# SheetPIC80_A9377.net
KiCad netlist of a schematic drawn in Altium Designer
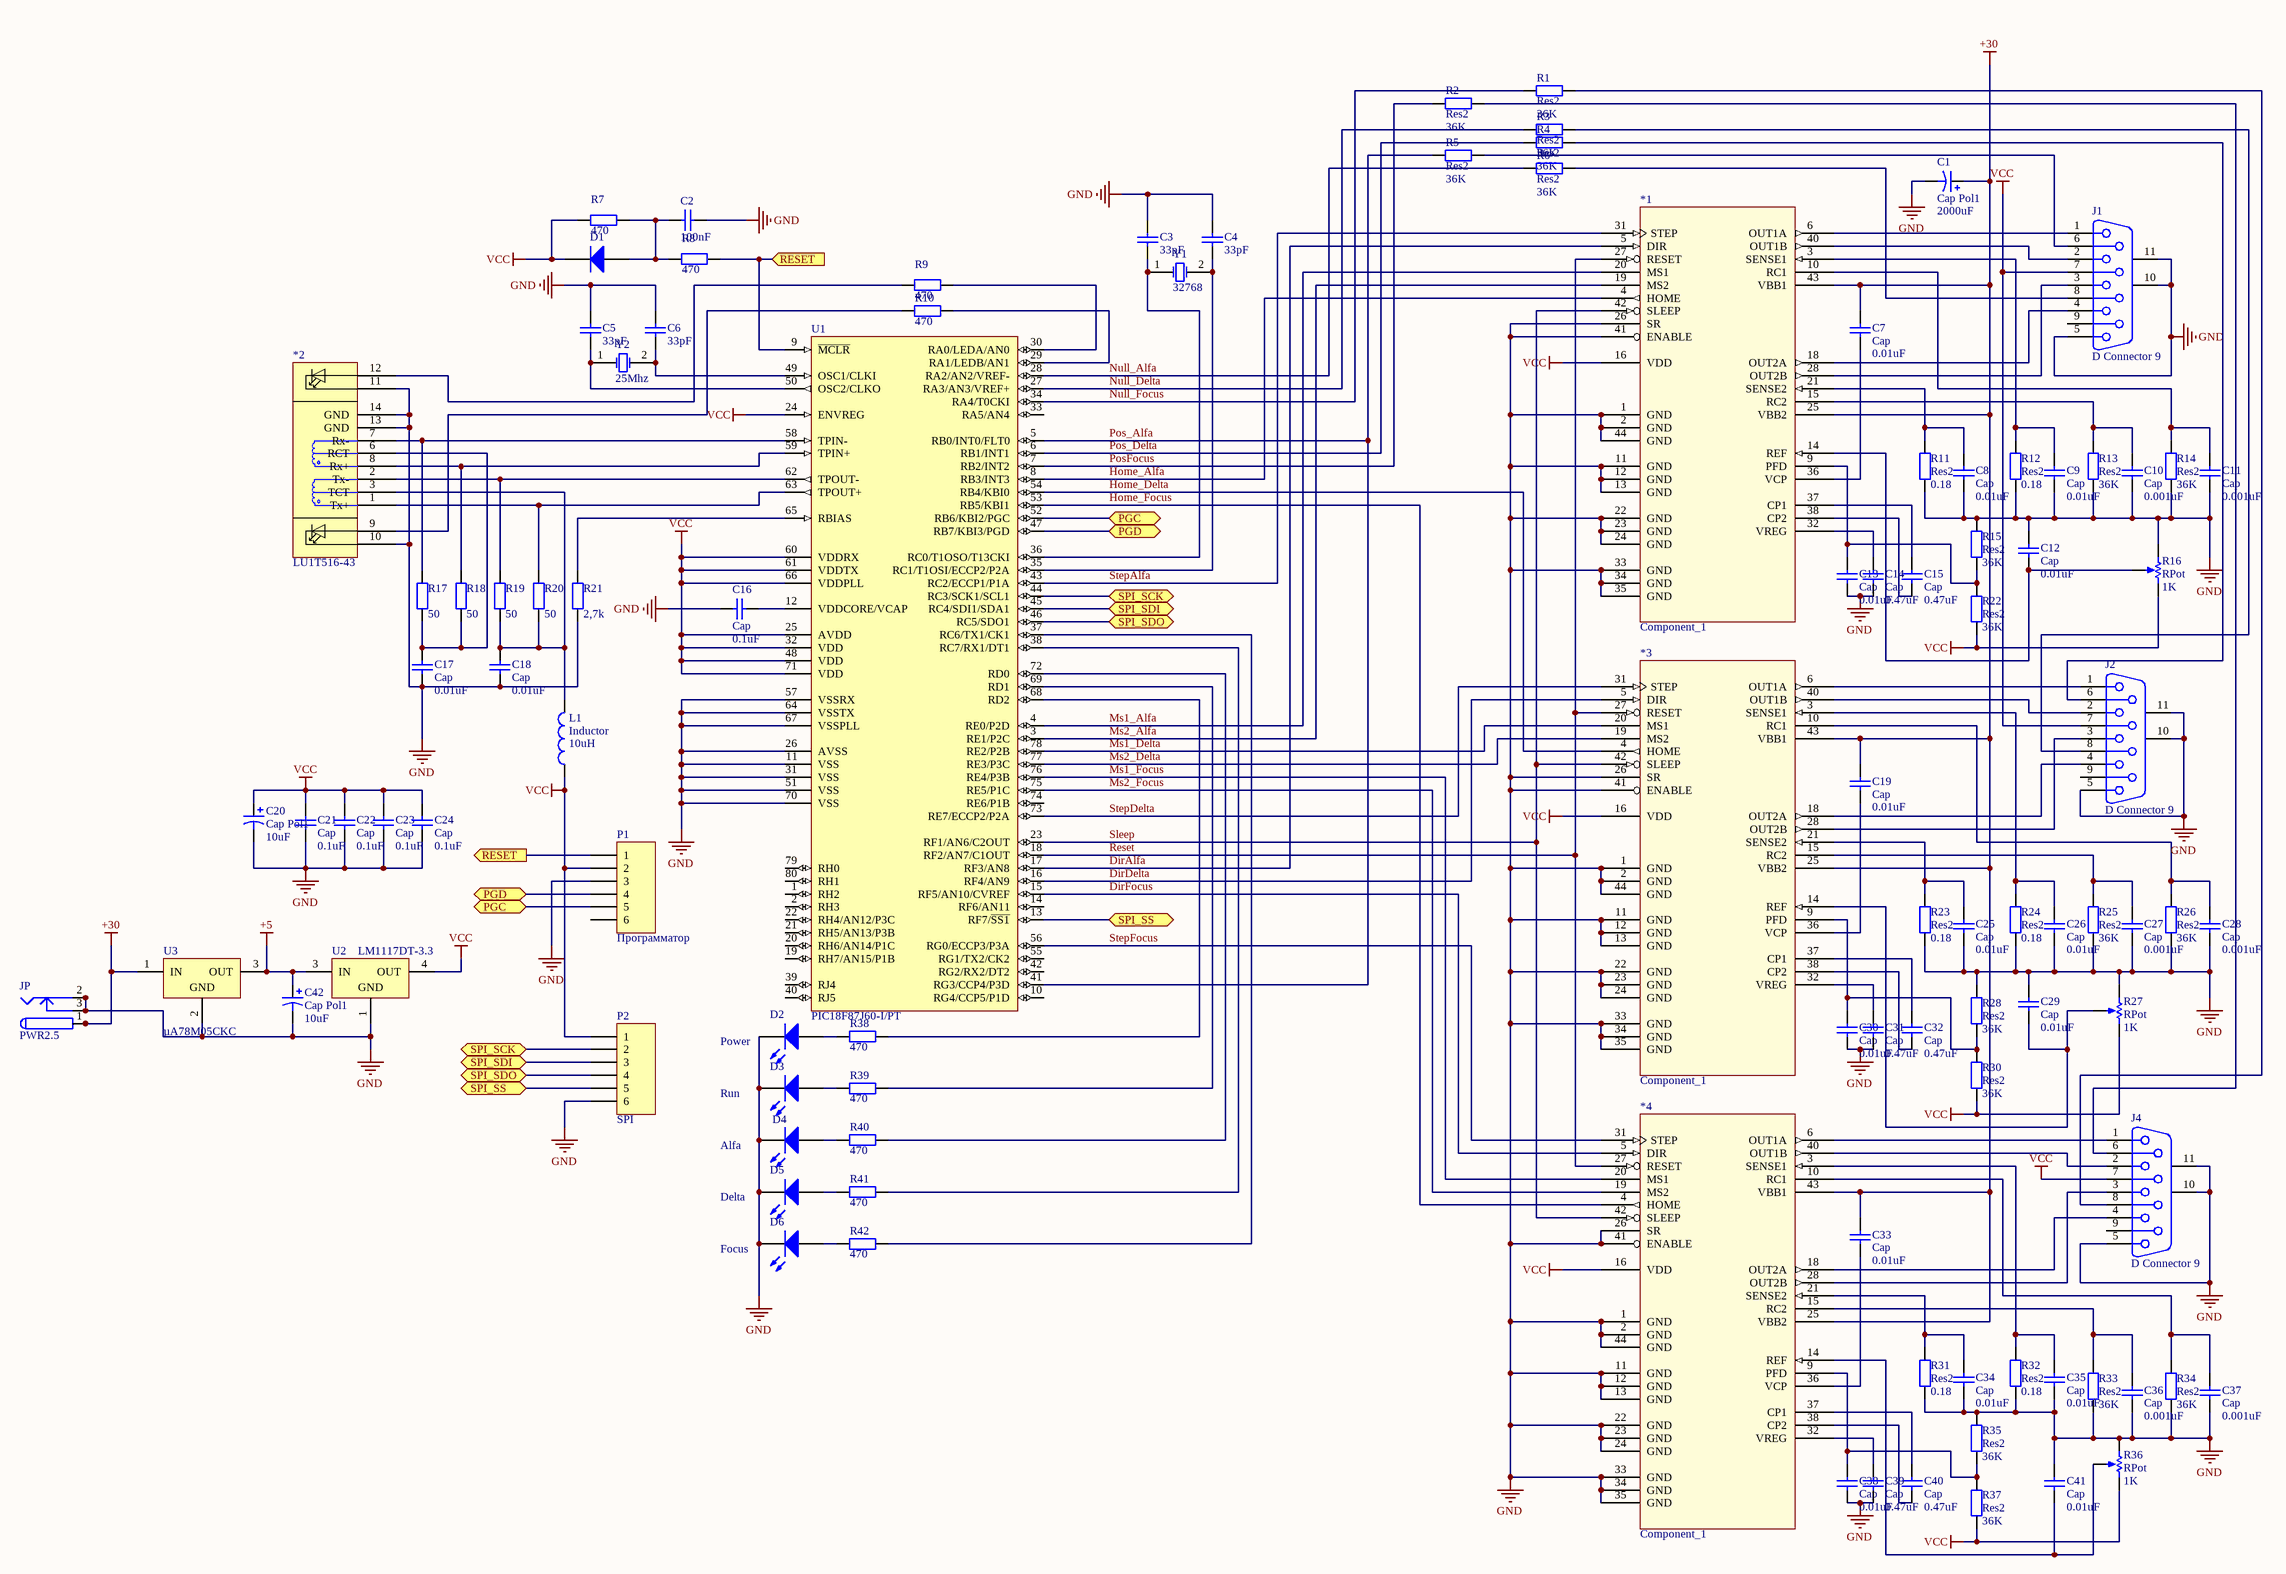
[diagram p0: SheetPIC80_A9377.SchDoc]

(export (version "E")
  (design (tool "Eeschema 10.0.6"))
  (components
    (comp (ref "*1")
      (value "Component_1")
      (footprint "PLCC-44AM")
      (libsource (lib "Allegro Stepper Control") (part "Component_1"))
    )
    (comp (ref "*2")
      (value "LU1T516-43")
      (footprint "EthernetCON")
      (libsource (lib "Ethernet") (part "LU1T516-43"))
    )
    (comp (ref "*3")
      (value "Component_1")
      (footprint "PLCC-44AM")
      (libsource (lib "Allegro Stepper Control") (part "Component_1"))
    )
    (comp (ref "*4")
      (value "Component_1")
      (footprint "PLCC-44AM")
      (libsource (lib "Allegro Stepper Control") (part "Component_1"))
    )
    (comp (ref "C1")
      (value "Cap Pol1")
      (footprint "RB7.6-15")
      (description "Polarized Capacitor (Radial)")
      (fields (field (name "ALTIUM_VALUE") "2000uF") (field (name "PUBLISHER") "Altium Limited"))
      (libsource (lib "Miscellaneous Devices") (part "Cap Pol1"))
    )
    (comp (ref "C2")
      (value "100nF")
      (footprint "CAPC3225N")
      (description "Capacitor")
      (fields (field (name "Comment") "Cap") (field (name "PUBLISHER") "Altium Limited"))
      (libsource (lib "Miscellaneous Devices") (part "Cap"))
    )
    (comp (ref "C3")
      (value "33pF")
      (footprint "CAPC2012L")
      (description "Capacitor")
      (fields (field (name "Comment") "Cap") (field (name "PUBLISHER") "Altium Limited"))
      (libsource (lib "Miscellaneous Devices") (part "Cap"))
    )
    (comp (ref "C4")
      (value "33pF")
      (footprint "CAPC2012L")
      (description "Capacitor")
      (fields (field (name "Comment") "Cap") (field (name "PUBLISHER") "Altium Limited"))
      (libsource (lib "Miscellaneous Devices") (part "Cap"))
    )
    (comp (ref "C5")
      (value "33pF")
      (footprint "CAPC2012L")
      (description "Capacitor")
      (fields (field (name "Comment") "Cap") (field (name "PUBLISHER") "Altium Limited"))
      (libsource (lib "Miscellaneous Devices") (part "Cap"))
    )
    (comp (ref "C6")
      (value "33pF")
      (footprint "CAPC2012L")
      (description "Capacitor")
      (fields (field (name "Comment") "Cap") (field (name "PUBLISHER") "Altium Limited"))
      (libsource (lib "Miscellaneous Devices") (part "Cap"))
    )
    (comp (ref "C7")
      (value "Cap")
      (footprint "RESC3225L")
      (description "Capacitor")
      (fields (field (name "ALTIUM_VALUE") "0.01uF") (field (name "PUBLISHER") "Altium Limited"))
      (libsource (lib "Miscellaneous Devices") (part "Cap"))
    )
    (comp (ref "C8")
      (value "Cap")
      (footprint "RESC3225L")
      (description "Capacitor")
      (fields (field (name "ALTIUM_VALUE") "0.01uF") (field (name "PUBLISHER") "Altium Limited"))
      (libsource (lib "Miscellaneous Devices") (part "Cap"))
    )
    (comp (ref "C9")
      (value "Cap")
      (footprint "RESC3225L")
      (description "Capacitor")
      (fields (field (name "ALTIUM_VALUE") "0.01uF") (field (name "PUBLISHER") "Altium Limited"))
      (libsource (lib "Miscellaneous Devices") (part "Cap"))
    )
    (comp (ref "C10")
      (value "Cap")
      (footprint "CAPC2012L")
      (description "Capacitor")
      (fields (field (name "ALTIUM_VALUE") "0.001uF") (field (name "PUBLISHER") "Altium Limited"))
      (libsource (lib "Miscellaneous Devices") (part "Cap"))
    )
    (comp (ref "C11")
      (value "Cap")
      (footprint "CAPC2012L")
      (description "Capacitor")
      (fields (field (name "ALTIUM_VALUE") "0.001uF") (field (name "PUBLISHER") "Altium Limited"))
      (libsource (lib "Miscellaneous Devices") (part "Cap"))
    )
    (comp (ref "C12")
      (value "Cap")
      (footprint "CAPC2012L")
      (description "Capacitor")
      (fields (field (name "ALTIUM_VALUE") "0.01uF") (field (name "PUBLISHER") "Altium Limited"))
      (libsource (lib "Miscellaneous Devices") (part "Cap"))
    )
    (comp (ref "C13")
      (value "Cap")
      (footprint "RESC2012N")
      (description "Capacitor")
      (fields (field (name "ALTIUM_VALUE") "0.01uF") (field (name "PUBLISHER") "Altium Limited"))
      (libsource (lib "Miscellaneous Devices") (part "Cap"))
    )
    (comp (ref "C14")
      (value "Cap")
      (footprint "RESC3225L")
      (description "Capacitor")
      (fields (field (name "ALTIUM_VALUE") "0.47uF") (field (name "PUBLISHER") "Altium Limited"))
      (libsource (lib "Miscellaneous Devices") (part "Cap"))
    )
    (comp (ref "C15")
      (value "Cap")
      (footprint "RESC3225L")
      (description "Capacitor")
      (fields (field (name "ALTIUM_VALUE") "0.47uF") (field (name "PUBLISHER") "Altium Limited"))
      (libsource (lib "Miscellaneous Devices") (part "Cap"))
    )
    (comp (ref "C16")
      (value "Cap")
      (footprint "CAPC3225L")
      (description "Capacitor")
      (fields (field (name "ALTIUM_VALUE") "0.1uF") (field (name "PUBLISHER") "Altium Limited"))
      (libsource (lib "Miscellaneous Devices") (part "Cap"))
    )
    (comp (ref "C17")
      (value "Cap")
      (footprint "CAPC3216L")
      (description "Capacitor")
      (fields (field (name "ALTIUM_VALUE") "0.01uF") (field (name "PUBLISHER") "Altium Limited"))
      (libsource (lib "Miscellaneous Devices") (part "Cap"))
    )
    (comp (ref "C18")
      (value "Cap")
      (footprint "CAPC3216L")
      (description "Capacitor")
      (fields (field (name "ALTIUM_VALUE") "0.01uF") (field (name "PUBLISHER") "Altium Limited"))
      (libsource (lib "Miscellaneous Devices") (part "Cap"))
    )
    (comp (ref "C19")
      (value "Cap")
      (footprint "RESC3225L")
      (description "Capacitor")
      (fields (field (name "ALTIUM_VALUE") "0.01uF") (field (name "PUBLISHER") "Altium Limited"))
      (libsource (lib "Miscellaneous Devices") (part "Cap"))
    )
    (comp (ref "C20")
      (value "Cap Pol1")
      (footprint "CAPPR5-5x5")
      (description "Polarized Capacitor (Radial)")
      (fields (field (name "ALTIUM_VALUE") "10uF") (field (name "PUBLISHER") "Altium Limited"))
      (libsource (lib "Miscellaneous Devices") (part "Cap Pol1"))
    )
    (comp (ref "C21")
      (value "Cap")
      (footprint "CAPC3225L")
      (description "Capacitor")
      (fields (field (name "ALTIUM_VALUE") "0.1uF") (field (name "PUBLISHER") "Altium Limited"))
      (libsource (lib "Miscellaneous Devices") (part "Cap"))
    )
    (comp (ref "C22")
      (value "Cap")
      (footprint "CAPC3225L")
      (description "Capacitor")
      (fields (field (name "ALTIUM_VALUE") "0.1uF") (field (name "PUBLISHER") "Altium Limited"))
      (libsource (lib "Miscellaneous Devices") (part "Cap"))
    )
    (comp (ref "C23")
      (value "Cap")
      (footprint "CAPC3225L")
      (description "Capacitor")
      (fields (field (name "ALTIUM_VALUE") "0.1uF") (field (name "PUBLISHER") "Altium Limited"))
      (libsource (lib "Miscellaneous Devices") (part "Cap"))
    )
    (comp (ref "C24")
      (value "Cap")
      (footprint "CAPC3225L")
      (description "Capacitor")
      (fields (field (name "ALTIUM_VALUE") "0.1uF") (field (name "PUBLISHER") "Altium Limited"))
      (libsource (lib "Miscellaneous Devices") (part "Cap"))
    )
    (comp (ref "C25")
      (value "Cap")
      (footprint "RESC3225L")
      (description "Capacitor")
      (fields (field (name "ALTIUM_VALUE") "0.01uF") (field (name "PUBLISHER") "Altium Limited"))
      (libsource (lib "Miscellaneous Devices") (part "Cap"))
    )
    (comp (ref "C26")
      (value "Cap")
      (footprint "RESC3225L")
      (description "Capacitor")
      (fields (field (name "ALTIUM_VALUE") "0.01uF") (field (name "PUBLISHER") "Altium Limited"))
      (libsource (lib "Miscellaneous Devices") (part "Cap"))
    )
    (comp (ref "C27")
      (value "Cap")
      (footprint "CAPC2012L")
      (description "Capacitor")
      (fields (field (name "ALTIUM_VALUE") "0.001uF") (field (name "PUBLISHER") "Altium Limited"))
      (libsource (lib "Miscellaneous Devices") (part "Cap"))
    )
    (comp (ref "C28")
      (value "Cap")
      (footprint "CAPC2012L")
      (description "Capacitor")
      (fields (field (name "ALTIUM_VALUE") "0.001uF") (field (name "PUBLISHER") "Altium Limited"))
      (libsource (lib "Miscellaneous Devices") (part "Cap"))
    )
    (comp (ref "C29")
      (value "Cap")
      (footprint "CAPC2012L")
      (description "Capacitor")
      (fields (field (name "ALTIUM_VALUE") "0.01uF") (field (name "PUBLISHER") "Altium Limited"))
      (libsource (lib "Miscellaneous Devices") (part "Cap"))
    )
    (comp (ref "C30")
      (value "Cap")
      (footprint "RESC2012N")
      (description "Capacitor")
      (fields (field (name "ALTIUM_VALUE") "0.01uF") (field (name "PUBLISHER") "Altium Limited"))
      (libsource (lib "Miscellaneous Devices") (part "Cap"))
    )
    (comp (ref "C31")
      (value "Cap")
      (footprint "RESC3225L")
      (description "Capacitor")
      (fields (field (name "ALTIUM_VALUE") "0.47uF") (field (name "PUBLISHER") "Altium Limited"))
      (libsource (lib "Miscellaneous Devices") (part "Cap"))
    )
    (comp (ref "C32")
      (value "Cap")
      (footprint "RESC3225L")
      (description "Capacitor")
      (fields (field (name "ALTIUM_VALUE") "0.47uF") (field (name "PUBLISHER") "Altium Limited"))
      (libsource (lib "Miscellaneous Devices") (part "Cap"))
    )
    (comp (ref "C33")
      (value "Cap")
      (footprint "RESC3225L")
      (description "Capacitor")
      (fields (field (name "ALTIUM_VALUE") "0.01uF") (field (name "PUBLISHER") "Altium Limited"))
      (libsource (lib "Miscellaneous Devices") (part "Cap"))
    )
    (comp (ref "C34")
      (value "Cap")
      (footprint "RESC3225L")
      (description "Capacitor")
      (fields (field (name "ALTIUM_VALUE") "0.01uF") (field (name "PUBLISHER") "Altium Limited"))
      (libsource (lib "Miscellaneous Devices") (part "Cap"))
    )
    (comp (ref "C35")
      (value "Cap")
      (footprint "RESC3225L")
      (description "Capacitor")
      (fields (field (name "ALTIUM_VALUE") "0.01uF") (field (name "PUBLISHER") "Altium Limited"))
      (libsource (lib "Miscellaneous Devices") (part "Cap"))
    )
    (comp (ref "C36")
      (value "Cap")
      (footprint "CAPC2012L")
      (description "Capacitor")
      (fields (field (name "ALTIUM_VALUE") "0.001uF") (field (name "PUBLISHER") "Altium Limited"))
      (libsource (lib "Miscellaneous Devices") (part "Cap"))
    )
    (comp (ref "C37")
      (value "Cap")
      (footprint "CAPC2012L")
      (description "Capacitor")
      (fields (field (name "ALTIUM_VALUE") "0.001uF") (field (name "PUBLISHER") "Altium Limited"))
      (libsource (lib "Miscellaneous Devices") (part "Cap"))
    )
    (comp (ref "C38")
      (value "Cap")
      (footprint "RESC2012N")
      (description "Capacitor")
      (fields (field (name "ALTIUM_VALUE") "0.01uF") (field (name "PUBLISHER") "Altium Limited"))
      (libsource (lib "Miscellaneous Devices") (part "Cap"))
    )
    (comp (ref "C39")
      (value "Cap")
      (footprint "RESC3225L")
      (description "Capacitor")
      (fields (field (name "ALTIUM_VALUE") "0.47uF") (field (name "PUBLISHER") "Altium Limited"))
      (libsource (lib "Miscellaneous Devices") (part "Cap"))
    )
    (comp (ref "C40")
      (value "Cap")
      (footprint "RESC3225L")
      (description "Capacitor")
      (fields (field (name "ALTIUM_VALUE") "0.47uF") (field (name "PUBLISHER") "Altium Limited"))
      (libsource (lib "Miscellaneous Devices") (part "Cap"))
    )
    (comp (ref "C41")
      (value "Cap")
      (footprint "CAPC2012L")
      (description "Capacitor")
      (fields (field (name "ALTIUM_VALUE") "0.01uF") (field (name "PUBLISHER") "Altium Limited"))
      (libsource (lib "Miscellaneous Devices") (part "Cap"))
    )
    (comp (ref "C42")
      (value "Cap Pol1")
      (footprint "CAPPR5-5x5")
      (description "Polarized Capacitor (Radial)")
      (fields (field (name "ALTIUM_VALUE") "10uF") (field (name "PUBLISHER") "Altium Limited"))
      (libsource (lib "Miscellaneous Devices") (part "Cap Pol1"))
    )
    (comp (ref "D1")
      (value "Diode")
      (footprint "SOT95P240-3N")
      (description "Default Diode")
      (fields (field (name "PUBLISHER") "Altium Limited"))
      (libsource (lib "Miscellaneous Devices") (part "Diode"))
    )
    (comp (ref "D2")
      (value "Power")
      (footprint "LED-1")
      (description "Typical RED GaAs LED")
      (fields (field (name "PUBLISHER") "Altium Limited"))
      (libsource (lib "Miscellaneous Devices") (part "LED1"))
    )
    (comp (ref "D3")
      (value "Run")
      (footprint "LED-1")
      (description "Typical RED GaAs LED")
      (fields (field (name "PUBLISHER") "Altium Limited"))
      (libsource (lib "Miscellaneous Devices") (part "LED1"))
    )
    (comp (ref "D4")
      (value "Alfa")
      (footprint "LED-1")
      (description "Typical RED GaAs LED")
      (fields (field (name "PUBLISHER") "Altium Limited"))
      (libsource (lib "Miscellaneous Devices") (part "LED1"))
    )
    (comp (ref "D5")
      (value "Delta")
      (footprint "LED-1")
      (description "Typical RED GaAs LED")
      (fields (field (name "PUBLISHER") "Altium Limited"))
      (libsource (lib "Miscellaneous Devices") (part "LED1"))
    )
    (comp (ref "D6")
      (value "Focus")
      (footprint "LED-1")
      (description "Typical RED GaAs LED")
      (fields (field (name "PUBLISHER") "Altium Limited"))
      (libsource (lib "Miscellaneous Devices") (part "LED1"))
    )
    (comp (ref "J1")
      (value "D Connector 9")
      (footprint "D-SUB-9")
      (description "Receptacle Assembly, 9 Position, Right Angle")
      (fields (field (name "PUBLISHER") "Altium Limited"))
      (libsource (lib "Miscellaneous Connectors") (part "D Connector 9"))
    )
    (comp (ref "J2")
      (value "D Connector 9")
      (footprint "D-SUB-9")
      (description "Receptacle Assembly, 9 Position, Right Angle")
      (fields (field (name "PUBLISHER") "Altium Limited"))
      (libsource (lib "Miscellaneous Connectors") (part "D Connector 9"))
    )
    (comp (ref "J4")
      (value "D Connector 9")
      (footprint "D-SUB-9")
      (description "Receptacle Assembly, 9 Position, Right Angle")
      (fields (field (name "PUBLISHER") "Altium Limited"))
      (libsource (lib "Miscellaneous Connectors") (part "D Connector 9"))
    )
    (comp (ref "JP")
      (value "PWR2.5")
      (footprint "KLD-0202")
      (description "Low Voltage Power Supply Connector")
      (fields (field (name "PUBLISHER") "Altium Limited"))
      (libsource (lib "Miscellaneous Connectors") (part "PWR2.5"))
    )
    (comp (ref "L1")
      (value "Inductor")
      (footprint "INDC3216AL")
      (fields (field (name "ALTIUM_VALUE") "10uH") (field (name "PUBLISHER") "Altium Limited"))
      (libsource (lib "Miscellaneous Devices") (part "Inductor"))
    )
    (comp (ref "P1")
      (value "Программатор")
      (footprint "HDR1X6")
      (description "Header, 6-Pin")
      (fields (field (name "PUBLISHER") "Altium Limited"))
      (libsource (lib "Miscellaneous Connectors") (part "Header 6"))
    )
    (comp (ref "P2")
      (value "SPI")
      (footprint "HDR1X6")
      (description "Header, 6-Pin")
      (fields (field (name "PUBLISHER") "Altium Limited"))
      (libsource (lib "Miscellaneous Connectors") (part "Header 6"))
    )
    (comp (ref "R1")
      (value "Res2")
      (footprint "RESC2012N")
      (description "Resistor")
      (fields (field (name "ALTIUM_VALUE") "36K") (field (name "PUBLISHER") "Altium Limited"))
      (libsource (lib "Miscellaneous Devices") (part "Res2"))
    )
    (comp (ref "R2")
      (value "Res2")
      (footprint "RESC2012N")
      (description "Resistor")
      (fields (field (name "ALTIUM_VALUE") "36K") (field (name "PUBLISHER") "Altium Limited"))
      (libsource (lib "Miscellaneous Devices") (part "Res2"))
    )
    (comp (ref "R3")
      (value "Res2")
      (footprint "RESC2012N")
      (description "Resistor")
      (fields (field (name "ALTIUM_VALUE") "36K") (field (name "PUBLISHER") "Altium Limited"))
      (libsource (lib "Miscellaneous Devices") (part "Res2"))
    )
    (comp (ref "R4")
      (value "Res2")
      (footprint "RESC2012N")
      (description "Resistor")
      (fields (field (name "ALTIUM_VALUE") "36K") (field (name "PUBLISHER") "Altium Limited"))
      (libsource (lib "Miscellaneous Devices") (part "Res2"))
    )
    (comp (ref "R5")
      (value "Res2")
      (footprint "RESC2012N")
      (description "Resistor")
      (fields (field (name "ALTIUM_VALUE") "36K") (field (name "PUBLISHER") "Altium Limited"))
      (libsource (lib "Miscellaneous Devices") (part "Res2"))
    )
    (comp (ref "R6")
      (value "Res2")
      (footprint "RESC2012N")
      (description "Resistor")
      (fields (field (name "ALTIUM_VALUE") "36K") (field (name "PUBLISHER") "Altium Limited"))
      (libsource (lib "Miscellaneous Devices") (part "Res2"))
    )
    (comp (ref "R7")
      (value "470")
      (footprint "RESC2012M")
      (description "Resistor")
      (fields (field (name "Comment") "Res2") (field (name "PUBLISHER") "Altium Limited"))
      (libsource (lib "Miscellaneous Devices") (part "Res2"))
    )
    (comp (ref "R8")
      (value "470")
      (footprint "RESC2012M")
      (description "Resistor")
      (fields (field (name "Comment") "Res2") (field (name "PUBLISHER") "Altium Limited"))
      (libsource (lib "Miscellaneous Devices") (part "Res2"))
    )
    (comp (ref "R9")
      (value "470")
      (footprint "RESC2012M")
      (description "Resistor")
      (fields (field (name "Comment") "Res2") (field (name "PUBLISHER") "Altium Limited"))
      (libsource (lib "Miscellaneous Devices") (part "Res2"))
    )
    (comp (ref "R10")
      (value "470")
      (footprint "RESC2012M")
      (description "Resistor")
      (fields (field (name "Comment") "Res2") (field (name "PUBLISHER") "Altium Limited"))
      (libsource (lib "Miscellaneous Devices") (part "Res2"))
    )
    (comp (ref "R11")
      (value "Res2")
      (footprint "AXIAL-0.5")
      (description "Resistor")
      (fields (field (name "ALTIUM_VALUE") "0.18") (field (name "PUBLISHER") "Altium Limited"))
      (libsource (lib "") (part "Res2_1"))
    )
    (comp (ref "R12")
      (value "Res2")
      (footprint "AXIAL-0.5")
      (description "Resistor")
      (fields (field (name "ALTIUM_VALUE") "0.18") (field (name "PUBLISHER") "Altium Limited"))
      (libsource (lib "") (part "Res2_1"))
    )
    (comp (ref "R13")
      (value "Res2")
      (footprint "RESC2012N")
      (description "Resistor")
      (fields (field (name "ALTIUM_VALUE") "36K") (field (name "PUBLISHER") "Altium Limited"))
      (libsource (lib "") (part "Res2_1"))
    )
    (comp (ref "R14")
      (value "Res2")
      (footprint "RESC2012N")
      (description "Resistor")
      (fields (field (name "ALTIUM_VALUE") "36K") (field (name "PUBLISHER") "Altium Limited"))
      (libsource (lib "") (part "Res2_1"))
    )
    (comp (ref "R15")
      (value "Res2")
      (footprint "RESC2012N")
      (description "Resistor")
      (fields (field (name "ALTIUM_VALUE") "36K") (field (name "PUBLISHER") "Altium Limited"))
      (libsource (lib "") (part "Res2_1"))
    )
    (comp (ref "R16")
      (value "RPot")
      (footprint "VR5")
      (description "Potentiometer")
      (fields (field (name "ALTIUM_VALUE") "1K") (field (name "PUBLISHER") "Altium Limited"))
      (libsource (lib "Miscellaneous Devices") (part "RPot"))
    )
    (comp (ref "R17")
      (value "50")
      (footprint "RESC2012M")
      (description "Resistor")
      (fields (field (name "Comment") "Res2") (field (name "PUBLISHER") "Altium Limited"))
      (libsource (lib "") (part "Res2_1"))
    )
    (comp (ref "R18")
      (value "50")
      (footprint "RESC2012M")
      (description "Resistor")
      (fields (field (name "Comment") "Res2") (field (name "PUBLISHER") "Altium Limited"))
      (libsource (lib "") (part "Res2_1"))
    )
    (comp (ref "R19")
      (value "50")
      (footprint "RESC2012M")
      (description "Resistor")
      (fields (field (name "Comment") "Res2") (field (name "PUBLISHER") "Altium Limited"))
      (libsource (lib "") (part "Res2_1"))
    )
    (comp (ref "R20")
      (value "50")
      (footprint "RESC2012M")
      (description "Resistor")
      (fields (field (name "Comment") "Res2") (field (name "PUBLISHER") "Altium Limited"))
      (libsource (lib "") (part "Res2_1"))
    )
    (comp (ref "R21")
      (value "2,7k")
      (footprint "RESC2012M")
      (description "Resistor")
      (fields (field (name "Comment") "Res2") (field (name "PUBLISHER") "Altium Limited"))
      (libsource (lib "") (part "Res2_1"))
    )
    (comp (ref "R22")
      (value "Res2")
      (footprint "RESC2012N")
      (description "Resistor")
      (fields (field (name "ALTIUM_VALUE") "36K") (field (name "PUBLISHER") "Altium Limited"))
      (libsource (lib "") (part "Res2_1"))
    )
    (comp (ref "R23")
      (value "Res2")
      (footprint "AXIAL-0.5")
      (description "Resistor")
      (fields (field (name "ALTIUM_VALUE") "0.18") (field (name "PUBLISHER") "Altium Limited"))
      (libsource (lib "") (part "Res2_1"))
    )
    (comp (ref "R24")
      (value "Res2")
      (footprint "AXIAL-0.5")
      (description "Resistor")
      (fields (field (name "ALTIUM_VALUE") "0.18") (field (name "PUBLISHER") "Altium Limited"))
      (libsource (lib "") (part "Res2_1"))
    )
    (comp (ref "R25")
      (value "Res2")
      (footprint "RESC2012N")
      (description "Resistor")
      (fields (field (name "ALTIUM_VALUE") "36K") (field (name "PUBLISHER") "Altium Limited"))
      (libsource (lib "") (part "Res2_1"))
    )
    (comp (ref "R26")
      (value "Res2")
      (footprint "RESC2012N")
      (description "Resistor")
      (fields (field (name "ALTIUM_VALUE") "36K") (field (name "PUBLISHER") "Altium Limited"))
      (libsource (lib "") (part "Res2_1"))
    )
    (comp (ref "R27")
      (value "RPot")
      (footprint "VR5")
      (description "Potentiometer")
      (fields (field (name "ALTIUM_VALUE") "1K") (field (name "PUBLISHER") "Altium Limited"))
      (libsource (lib "Miscellaneous Devices") (part "RPot"))
    )
    (comp (ref "R28")
      (value "Res2")
      (footprint "RESC2012N")
      (description "Resistor")
      (fields (field (name "ALTIUM_VALUE") "36K") (field (name "PUBLISHER") "Altium Limited"))
      (libsource (lib "") (part "Res2_1"))
    )
    (comp (ref "R30")
      (value "Res2")
      (footprint "RESC2012N")
      (description "Resistor")
      (fields (field (name "ALTIUM_VALUE") "36K") (field (name "PUBLISHER") "Altium Limited"))
      (libsource (lib "") (part "Res2_1"))
    )
    (comp (ref "R31")
      (value "Res2")
      (footprint "AXIAL-0.5")
      (description "Resistor")
      (fields (field (name "ALTIUM_VALUE") "0.18") (field (name "PUBLISHER") "Altium Limited"))
      (libsource (lib "") (part "Res2_1"))
    )
    (comp (ref "R32")
      (value "Res2")
      (footprint "AXIAL-0.5")
      (description "Resistor")
      (fields (field (name "ALTIUM_VALUE") "0.18") (field (name "PUBLISHER") "Altium Limited"))
      (libsource (lib "") (part "Res2_1"))
    )
    (comp (ref "R33")
      (value "Res2")
      (footprint "RESC2012N")
      (description "Resistor")
      (fields (field (name "ALTIUM_VALUE") "36K") (field (name "PUBLISHER") "Altium Limited"))
      (libsource (lib "") (part "Res2_1"))
    )
    (comp (ref "R34")
      (value "Res2")
      (footprint "RESC2012N")
      (description "Resistor")
      (fields (field (name "ALTIUM_VALUE") "36K") (field (name "PUBLISHER") "Altium Limited"))
      (libsource (lib "") (part "Res2_1"))
    )
    (comp (ref "R35")
      (value "Res2")
      (footprint "RESC2012N")
      (description "Resistor")
      (fields (field (name "ALTIUM_VALUE") "36K") (field (name "PUBLISHER") "Altium Limited"))
      (libsource (lib "") (part "Res2_1"))
    )
    (comp (ref "R36")
      (value "RPot")
      (footprint "VR5")
      (description "Potentiometer")
      (fields (field (name "ALTIUM_VALUE") "1K") (field (name "PUBLISHER") "Altium Limited"))
      (libsource (lib "Miscellaneous Devices") (part "RPot"))
    )
    (comp (ref "R37")
      (value "Res2")
      (footprint "RESC2012N")
      (description "Resistor")
      (fields (field (name "ALTIUM_VALUE") "36K") (field (name "PUBLISHER") "Altium Limited"))
      (libsource (lib "") (part "Res2_1"))
    )
    (comp (ref "R38")
      (value "470")
      (footprint "RESC2012M")
      (description "Resistor")
      (fields (field (name "Comment") "Res2") (field (name "PUBLISHER") "Altium Limited"))
      (libsource (lib "Miscellaneous Devices") (part "Res2"))
    )
    (comp (ref "R39")
      (value "470")
      (footprint "RESC2012M")
      (description "Resistor")
      (fields (field (name "Comment") "Res2") (field (name "PUBLISHER") "Altium Limited"))
      (libsource (lib "Miscellaneous Devices") (part "Res2"))
    )
    (comp (ref "R40")
      (value "470")
      (footprint "RESC2012M")
      (description "Resistor")
      (fields (field (name "Comment") "Res2") (field (name "PUBLISHER") "Altium Limited"))
      (libsource (lib "Miscellaneous Devices") (part "Res2"))
    )
    (comp (ref "R41")
      (value "470")
      (footprint "RESC2012M")
      (description "Resistor")
      (fields (field (name "Comment") "Res2") (field (name "PUBLISHER") "Altium Limited"))
      (libsource (lib "Miscellaneous Devices") (part "Res2"))
    )
    (comp (ref "R42")
      (value "470")
      (footprint "RESC2012M")
      (description "Resistor")
      (fields (field (name "Comment") "Res2") (field (name "PUBLISHER") "Altium Limited"))
      (libsource (lib "Miscellaneous Devices") (part "Res2"))
    )
    (comp (ref "U1")
      (value "PIC18F87J60-I/PT")
      (footprint "TQFP-PT80_N")
      (fields (field (name "PUBLISHER") "Altium Limited"))
      (libsource (lib "Microchip Microcontroller 8-Bit PIC18") (part "PIC18F87J60-I/PT"))
    )
    (comp (ref "U2")
      (value "LM1117DT-3.3")
      (footprint "TD03B_N")
      (description "800mA Low-Dropout Linear Regulator")
      (fields
        (field (name "MANUFACTURER") "National Semiconductor")
        (field (name "DIGIKEYPARTNUMBER") "LM1117DT-3.3-ND")
        (field (name "PUBLISHER") "Altium Limited")
      )
      (libsource (lib "NSC LDO") (part "LM1117DT-3.3"))
    )
    (comp (ref "U3")
      (value "µA78M05CKC")
      (footprint "KC03")
      (description "Positive-Voltage Regulator")
      (fields (field (name "PUBLISHER") "Altium Limited"))
      (libsource (lib "TI Power Mgt Voltage Regulator") (part "µA78M05CKC"))
    )
    (comp (ref "Y1")
      (value "32768")
      (footprint "Quartz")
      (description "Crystal Oscillator")
      (fields (field (name "Comment") "XTAL") (field (name "PUBLISHER") "Altium Limited"))
      (libsource (lib "Miscellaneous Devices") (part "XTAL"))
    )
    (comp (ref "Y2")
      (value "25Mhz")
      (footprint "Quartz")
      (description "Crystal Oscillator")
      (fields (field (name "Comment") "XTAL") (field (name "PUBLISHER") "Altium Limited"))
      (libsource (lib "Miscellaneous Devices") (part "XTAL"))
    )
  )
  (nets
    (net (code "1") (name "+5") (class "Default")
      (node (ref "C42") (pin "1") (pinfunction "1_1") (pintype "passive"))
      (node (ref "U2") (pin "3") (pinfunction "IN_3") (pintype "power_in"))
      (node (ref "U3") (pin "3") (pinfunction "OUT_3") (pintype "power_in"))
    )
    (net (code "2") (name "+30") (class "Default")
      (node (ref "*1") (pin "25") (pinfunction "VBB2_25") (pintype "power_in"))
      (node (ref "*1") (pin "43") (pinfunction "VBB1_43") (pintype "power_in"))
      (node (ref "*3") (pin "25") (pinfunction "VBB2_25") (pintype "power_in"))
      (node (ref "*3") (pin "43") (pinfunction "VBB1_43") (pintype "power_in"))
      (node (ref "*4") (pin "25") (pinfunction "VBB2_25") (pintype "power_in"))
      (node (ref "*4") (pin "43") (pinfunction "VBB1_43") (pintype "power_in"))
      (node (ref "C1") (pin "1") (pinfunction "1_1") (pintype "passive"))
      (node (ref "C19") (pin "2") (pinfunction "2_2") (pintype "passive"))
      (node (ref "C33") (pin "2") (pinfunction "2_2") (pintype "passive"))
      (node (ref "C7") (pin "2") (pinfunction "2_2") (pintype "passive"))
      (node (ref "JP") (pin "1") (pinfunction "1_1") (pintype "power_in"))
      (node (ref "JP") (pin "1A") (pinfunction "1A_1A") (pintype "power_in"))
      (node (ref "JP") (pin "1B") (pinfunction "1B_1B") (pintype "power_in"))
      (node (ref "U3") (pin "1") (pinfunction "IN_1") (pintype "power_in"))
    )
    (net (code "3") (name "/DirAlfa") (class "Default")
      (node (ref "*1") (pin "5") (pinfunction "DIR_5") (pintype "input"))
      (node (ref "U1") (pin "17") (pinfunction "RF3/AN8_17") (pintype "bidirectional"))
    )
    (net (code "4") (name "/DirDelta") (class "Default")
      (node (ref "*3") (pin "5") (pinfunction "DIR_5") (pintype "input"))
      (node (ref "U1") (pin "16") (pinfunction "RF4/AN9_16") (pintype "bidirectional"))
    )
    (net (code "5") (name "/DirFocus") (class "Default")
      (node (ref "*4") (pin "5") (pinfunction "DIR_5") (pintype "input"))
      (node (ref "U1") (pin "15") (pinfunction "RF5/AN10/CVREF_15") (pintype "bidirectional"))
    )
    (net (code "6") (name "/Home_Alfa") (class "Default")
      (node (ref "*1") (pin "4") (pinfunction "HOME_4") (pintype "output"))
      (node (ref "U1") (pin "8") (pinfunction "RB3/INT3_8") (pintype "bidirectional"))
    )
    (net (code "7") (name "/Home_Delta") (class "Default")
      (node (ref "*3") (pin "4") (pinfunction "HOME_4") (pintype "output"))
      (node (ref "U1") (pin "54") (pinfunction "RB4/KBI0_54") (pintype "bidirectional"))
    )
    (net (code "8") (name "/Home_Focus") (class "Default")
      (node (ref "*4") (pin "4") (pinfunction "HOME_4") (pintype "output"))
      (node (ref "U1") (pin "53") (pinfunction "RB5/KBI1_53") (pintype "bidirectional"))
    )
    (net (code "9") (name "/Ms1_Alfa") (class "Default")
      (node (ref "*1") (pin "20") (pinfunction "MS1_20") (pintype "passive"))
      (node (ref "U1") (pin "4") (pinfunction "RE0/P2D_4") (pintype "bidirectional"))
    )
    (net (code "10") (name "/Ms1_Delta") (class "Default")
      (node (ref "*3") (pin "20") (pinfunction "MS1_20") (pintype "passive"))
      (node (ref "U1") (pin "78") (pinfunction "RE2/P2B_78") (pintype "bidirectional"))
    )
    (net (code "11") (name "/Ms1_Focus") (class "Default")
      (node (ref "*4") (pin "20") (pinfunction "MS1_20") (pintype "passive"))
      (node (ref "U1") (pin "76") (pinfunction "RE4/P3B_76") (pintype "bidirectional"))
    )
    (net (code "12") (name "/Ms2_Alfa") (class "Default")
      (node (ref "*1") (pin "19") (pinfunction "MS2_19") (pintype "passive"))
      (node (ref "U1") (pin "3") (pinfunction "RE1/P2C_3") (pintype "bidirectional"))
    )
    (net (code "13") (name "/Ms2_Delta") (class "Default")
      (node (ref "*3") (pin "19") (pinfunction "MS2_19") (pintype "passive"))
      (node (ref "U1") (pin "77") (pinfunction "RE3/P3C_77") (pintype "bidirectional"))
    )
    (net (code "14") (name "/Ms2_Focus") (class "Default")
      (node (ref "*4") (pin "19") (pinfunction "MS2_19") (pintype "passive"))
      (node (ref "U1") (pin "75") (pinfunction "RE5/P1C_75") (pintype "bidirectional"))
    )
    (net (code "15") (name "/Null_Alfa") (class "Default")
      (node (ref "R6") (pin "2") (pinfunction "2_2") (pintype "passive"))
      (node (ref "U1") (pin "28") (pinfunction "RA2/AN2/VREF-_28") (pintype "bidirectional"))
    )
    (net (code "16") (name "/Null_Delta") (class "Default")
      (node (ref "R3") (pin "2") (pinfunction "2_2") (pintype "passive"))
      (node (ref "U1") (pin "27") (pinfunction "RA3/AN3/VREF+_27") (pintype "bidirectional"))
    )
    (net (code "17") (name "/Null_Focus") (class "Default")
      (node (ref "R1") (pin "2") (pinfunction "2_2") (pintype "passive"))
      (node (ref "U1") (pin "34") (pinfunction "RA4/T0CKI_34") (pintype "bidirectional"))
    )
    (net (code "18") (name "/PGC") (class "Default")
      (node (ref "P1") (pin "5") (pinfunction "5_5") (pintype "passive"))
      (node (ref "U1") (pin "52") (pinfunction "RB6/KBI2/PGC_52") (pintype "bidirectional"))
    )
    (net (code "19") (name "/PGD") (class "Default")
      (node (ref "P1") (pin "4") (pinfunction "4_4") (pintype "passive"))
      (node (ref "U1") (pin "47") (pinfunction "RB7/KBI3/PGD_47") (pintype "bidirectional"))
    )
    (net (code "20") (name "/PosFocus") (class "Default")
      (node (ref "R2") (pin "2") (pinfunction "2_2") (pintype "passive"))
      (node (ref "U1") (pin "7") (pinfunction "RB2/INT2_7") (pintype "bidirectional"))
    )
    (net (code "21") (name "/Pos_Alfa") (class "Default")
      (node (ref "R5") (pin "2") (pinfunction "2_2") (pintype "passive"))
      (node (ref "U1") (pin "41") (pinfunction "RG3/CCP4/P3D_41") (pintype "bidirectional"))
      (node (ref "U1") (pin "5") (pinfunction "RB0/INT0/FLT0_5") (pintype "bidirectional"))
    )
    (net (code "22") (name "/Pos_Delta") (class "Default")
      (node (ref "R4") (pin "2") (pinfunction "2_2") (pintype "passive"))
      (node (ref "U1") (pin "6") (pinfunction "RB1/INT1_6") (pintype "bidirectional"))
    )
    (net (code "23") (name "/RESET") (class "Default")
      (node (ref "P1") (pin "1") (pinfunction "1_1") (pintype "passive"))
      (node (ref "R8") (pin "1") (pinfunction "1_1") (pintype "passive"))
      (node (ref "U1") (pin "9") (pinfunction "~{MCLR}_9") (pintype "input"))
    )
    (net (code "24") (name "/Reset") (class "Default")
      (node (ref "*1") (pin "27") (pinfunction "RESET_27") (pintype "input"))
      (node (ref "*3") (pin "27") (pinfunction "RESET_27") (pintype "input"))
      (node (ref "*4") (pin "27") (pinfunction "RESET_27") (pintype "input"))
      (node (ref "U1") (pin "18") (pinfunction "RF2/AN7/C1OUT_18") (pintype "bidirectional"))
    )
    (net (code "25") (name "/SPI_SCK") (class "Default")
      (node (ref "P2") (pin "2") (pinfunction "2_2") (pintype "passive"))
      (node (ref "U1") (pin "44") (pinfunction "RC3/SCK1/SCL1_44") (pintype "bidirectional"))
    )
    (net (code "26") (name "/SPI_SDI") (class "Default")
      (node (ref "P2") (pin "3") (pinfunction "3_3") (pintype "passive"))
      (node (ref "U1") (pin "45") (pinfunction "RC4/SDI1/SDA1_45") (pintype "bidirectional"))
    )
    (net (code "27") (name "/SPI_SDO") (class "Default")
      (node (ref "P2") (pin "4") (pinfunction "4_4") (pintype "passive"))
      (node (ref "U1") (pin "46") (pinfunction "RC5/SDO1_46") (pintype "bidirectional"))
    )
    (net (code "28") (name "/SPI_SS") (class "Default")
      (node (ref "P2") (pin "5") (pinfunction "5_5") (pintype "passive"))
      (node (ref "U1") (pin "13") (pinfunction "RF7/~{SS1}_13") (pintype "bidirectional"))
    )
    (net (code "29") (name "/Sleep") (class "Default")
      (node (ref "*1") (pin "42") (pinfunction "SLEEP_42") (pintype "input"))
      (node (ref "*3") (pin "42") (pinfunction "SLEEP_42") (pintype "input"))
      (node (ref "*4") (pin "42") (pinfunction "SLEEP_42") (pintype "input"))
      (node (ref "U1") (pin "23") (pinfunction "RF1/AN6/C2OUT_23") (pintype "bidirectional"))
    )
    (net (code "30") (name "/StepAlfa") (class "Default")
      (node (ref "*1") (pin "31") (pinfunction "STEP_31") (pintype "input"))
      (node (ref "U1") (pin "43") (pinfunction "RC2/ECCP1/P1A_43") (pintype "bidirectional"))
    )
    (net (code "31") (name "/StepDelta") (class "Default")
      (node (ref "*3") (pin "31") (pinfunction "STEP_31") (pintype "input"))
      (node (ref "U1") (pin "73") (pinfunction "RE7/ECCP2/P2A_73") (pintype "bidirectional"))
    )
    (net (code "32") (name "/StepFocus") (class "Default")
      (node (ref "*4") (pin "31") (pinfunction "STEP_31") (pintype "input"))
      (node (ref "U1") (pin "56") (pinfunction "RG0/ECCP3/P3A_56") (pintype "bidirectional"))
    )
    (net (code "33") (name "GND") (class "Default")
      (node (ref "*1") (pin "1") (pinfunction "GND_1") (pintype "power_in"))
      (node (ref "*1") (pin "11") (pinfunction "GND_11") (pintype "power_in"))
      (node (ref "*1") (pin "12") (pinfunction "GND_12") (pintype "power_in"))
      (node (ref "*1") (pin "13") (pinfunction "GND_13") (pintype "power_in"))
      (node (ref "*1") (pin "2") (pinfunction "GND_2") (pintype "power_in"))
      (node (ref "*1") (pin "22") (pinfunction "GND_22") (pintype "power_in"))
      (node (ref "*1") (pin "23") (pinfunction "GND_23") (pintype "power_in"))
      (node (ref "*1") (pin "24") (pinfunction "GND_24") (pintype "power_in"))
      (node (ref "*1") (pin "26") (pinfunction "SR_26") (pintype "passive"))
      (node (ref "*1") (pin "33") (pinfunction "GND_33") (pintype "power_in"))
      (node (ref "*1") (pin "34") (pinfunction "GND_34") (pintype "power_in"))
      (node (ref "*1") (pin "35") (pinfunction "GND_35") (pintype "power_in"))
      (node (ref "*1") (pin "41") (pinfunction "ENABLE_41") (pintype "passive"))
      (node (ref "*1") (pin "44") (pinfunction "GND_44") (pintype "power_in"))
      (node (ref "*2") (pin "10") (pintype "passive"))
      (node (ref "*2") (pin "11") (pintype "passive"))
      (node (ref "*2") (pin "13") (pinfunction "GND_13") (pintype "passive"))
      (node (ref "*2") (pin "14") (pinfunction "GND_14") (pintype "passive"))
      (node (ref "*3") (pin "1") (pinfunction "GND_1") (pintype "power_in"))
      (node (ref "*3") (pin "11") (pinfunction "GND_11") (pintype "power_in"))
      (node (ref "*3") (pin "12") (pinfunction "GND_12") (pintype "power_in"))
      (node (ref "*3") (pin "13") (pinfunction "GND_13") (pintype "power_in"))
      (node (ref "*3") (pin "2") (pinfunction "GND_2") (pintype "power_in"))
      (node (ref "*3") (pin "22") (pinfunction "GND_22") (pintype "power_in"))
      (node (ref "*3") (pin "23") (pinfunction "GND_23") (pintype "power_in"))
      (node (ref "*3") (pin "24") (pinfunction "GND_24") (pintype "power_in"))
      (node (ref "*3") (pin "26") (pinfunction "SR_26") (pintype "passive"))
      (node (ref "*3") (pin "33") (pinfunction "GND_33") (pintype "power_in"))
      (node (ref "*3") (pin "34") (pinfunction "GND_34") (pintype "power_in"))
      (node (ref "*3") (pin "35") (pinfunction "GND_35") (pintype "power_in"))
      (node (ref "*3") (pin "41") (pinfunction "ENABLE_41") (pintype "passive"))
      (node (ref "*3") (pin "44") (pinfunction "GND_44") (pintype "power_in"))
      (node (ref "*4") (pin "1") (pinfunction "GND_1") (pintype "power_in"))
      (node (ref "*4") (pin "11") (pinfunction "GND_11") (pintype "power_in"))
      (node (ref "*4") (pin "12") (pinfunction "GND_12") (pintype "power_in"))
      (node (ref "*4") (pin "13") (pinfunction "GND_13") (pintype "power_in"))
      (node (ref "*4") (pin "2") (pinfunction "GND_2") (pintype "power_in"))
      (node (ref "*4") (pin "22") (pinfunction "GND_22") (pintype "power_in"))
      (node (ref "*4") (pin "23") (pinfunction "GND_23") (pintype "power_in"))
      (node (ref "*4") (pin "24") (pinfunction "GND_24") (pintype "power_in"))
      (node (ref "*4") (pin "26") (pinfunction "SR_26") (pintype "passive"))
      (node (ref "*4") (pin "33") (pinfunction "GND_33") (pintype "power_in"))
      (node (ref "*4") (pin "34") (pinfunction "GND_34") (pintype "power_in"))
      (node (ref "*4") (pin "35") (pinfunction "GND_35") (pintype "power_in"))
      (node (ref "*4") (pin "41") (pinfunction "ENABLE_41") (pintype "passive"))
      (node (ref "*4") (pin "44") (pinfunction "GND_44") (pintype "power_in"))
      (node (ref "C1") (pin "2") (pinfunction "2_2") (pintype "passive"))
      (node (ref "C10") (pin "1") (pinfunction "1_1") (pintype "passive"))
      (node (ref "C11") (pin "1") (pinfunction "1_1") (pintype "passive"))
      (node (ref "C12") (pin "2") (pinfunction "2_2") (pintype "passive"))
      (node (ref "C13") (pin "1") (pinfunction "1_1") (pintype "passive"))
      (node (ref "C14") (pin "1") (pinfunction "1_1") (pintype "passive"))
      (node (ref "C16") (pin "2") (pinfunction "2_2") (pintype "passive"))
      (node (ref "C17") (pin "1") (pinfunction "1_1") (pintype "passive"))
      (node (ref "C18") (pin "1") (pinfunction "1_1") (pintype "passive"))
      (node (ref "C2") (pin "1") (pinfunction "1_1") (pintype "passive"))
      (node (ref "C20") (pin "2") (pinfunction "2_2") (pintype "passive"))
      (node (ref "C21") (pin "2") (pinfunction "2_2") (pintype "passive"))
      (node (ref "C22") (pin "2") (pinfunction "2_2") (pintype "passive"))
      (node (ref "C23") (pin "2") (pinfunction "2_2") (pintype "passive"))
      (node (ref "C24") (pin "2") (pinfunction "2_2") (pintype "passive"))
      (node (ref "C25") (pin "1") (pinfunction "1_1") (pintype "passive"))
      (node (ref "C26") (pin "1") (pinfunction "1_1") (pintype "passive"))
      (node (ref "C27") (pin "1") (pinfunction "1_1") (pintype "passive"))
      (node (ref "C28") (pin "1") (pinfunction "1_1") (pintype "passive"))
      (node (ref "C29") (pin "2") (pinfunction "2_2") (pintype "passive"))
      (node (ref "C3") (pin "2") (pinfunction "2_2") (pintype "passive"))
      (node (ref "C30") (pin "1") (pinfunction "1_1") (pintype "passive"))
      (node (ref "C31") (pin "1") (pinfunction "1_1") (pintype "passive"))
      (node (ref "C34") (pin "1") (pinfunction "1_1") (pintype "passive"))
      (node (ref "C35") (pin "1") (pinfunction "1_1") (pintype "passive"))
      (node (ref "C36") (pin "1") (pinfunction "1_1") (pintype "passive"))
      (node (ref "C37") (pin "1") (pinfunction "1_1") (pintype "passive"))
      (node (ref "C38") (pin "1") (pinfunction "1_1") (pintype "passive"))
      (node (ref "C39") (pin "1") (pinfunction "1_1") (pintype "passive"))
      (node (ref "C4") (pin "1") (pinfunction "1_1") (pintype "passive"))
      (node (ref "C41") (pin "2") (pinfunction "2_2") (pintype "passive"))
      (node (ref "C42") (pin "2") (pinfunction "2_2") (pintype "passive"))
      (node (ref "C5") (pin "2") (pinfunction "2_2") (pintype "passive"))
      (node (ref "C6") (pin "1") (pinfunction "1_1") (pintype "passive"))
      (node (ref "C8") (pin "1") (pinfunction "1_1") (pintype "passive"))
      (node (ref "C9") (pin "1") (pinfunction "1_1") (pintype "passive"))
      (node (ref "D2") (pin "2") (pinfunction "K_2") (pintype "passive"))
      (node (ref "D3") (pin "2") (pinfunction "K_2") (pintype "passive"))
      (node (ref "D4") (pin "2") (pinfunction "K_2") (pintype "passive"))
      (node (ref "D5") (pin "2") (pinfunction "K_2") (pintype "passive"))
      (node (ref "D6") (pin "2") (pinfunction "K_2") (pintype "passive"))
      (node (ref "J1") (pin "10") (pinfunction "MH1_10") (pintype "passive"))
      (node (ref "J1") (pin "11") (pinfunction "MH2_11") (pintype "passive"))
      (node (ref "J1") (pin "5") (pinfunction "5_5") (pintype "passive"))
      (node (ref "J2") (pin "10") (pinfunction "MH1_10") (pintype "passive"))
      (node (ref "J2") (pin "11") (pinfunction "MH2_11") (pintype "passive"))
      (node (ref "J2") (pin "5") (pinfunction "5_5") (pintype "passive"))
      (node (ref "J4") (pin "10") (pinfunction "MH1_10") (pintype "passive"))
      (node (ref "J4") (pin "11") (pinfunction "MH2_11") (pintype "passive"))
      (node (ref "J4") (pin "5") (pinfunction "5_5") (pintype "passive"))
      (node (ref "JP") (pin "2") (pinfunction "2_2") (pintype "power_in"))
      (node (ref "JP") (pin "2A") (pinfunction "2A_2A") (pintype "power_in"))
      (node (ref "JP") (pin "2B") (pinfunction "2B_2B") (pintype "power_in"))
      (node (ref "JP") (pin "3") (pinfunction "3_3") (pintype "power_in"))
      (node (ref "JP") (pin "3A") (pinfunction "3A_3A") (pintype "power_in"))
      (node (ref "JP") (pin "3B") (pinfunction "3B_3B") (pintype "power_in"))
      (node (ref "P1") (pin "3") (pinfunction "3_3") (pintype "passive"))
      (node (ref "P2") (pin "6") (pinfunction "6_6") (pintype "passive"))
      (node (ref "R11") (pin "1") (pinfunction "1_1") (pintype "passive"))
      (node (ref "R12") (pin "1") (pinfunction "1_1") (pintype "passive"))
      (node (ref "R13") (pin "1") (pinfunction "1_1") (pintype "passive"))
      (node (ref "R14") (pin "1") (pinfunction "1_1") (pintype "passive"))
      (node (ref "R15") (pin "2") (pinfunction "2_2") (pintype "passive"))
      (node (ref "R16") (pin "1") (pinfunction "TOP_1") (pintype "passive"))
      (node (ref "R21") (pin "1") (pinfunction "1_1") (pintype "passive"))
      (node (ref "R23") (pin "1") (pinfunction "1_1") (pintype "passive"))
      (node (ref "R24") (pin "1") (pinfunction "1_1") (pintype "passive"))
      (node (ref "R25") (pin "1") (pinfunction "1_1") (pintype "passive"))
      (node (ref "R26") (pin "1") (pinfunction "1_1") (pintype "passive"))
      (node (ref "R27") (pin "1") (pinfunction "TOP_1") (pintype "passive"))
      (node (ref "R28") (pin "2") (pinfunction "2_2") (pintype "passive"))
      (node (ref "R31") (pin "1") (pinfunction "1_1") (pintype "passive"))
      (node (ref "R32") (pin "1") (pinfunction "1_1") (pintype "passive"))
      (node (ref "R33") (pin "1") (pinfunction "1_1") (pintype "passive"))
      (node (ref "R34") (pin "1") (pinfunction "1_1") (pintype "passive"))
      (node (ref "R35") (pin "2") (pinfunction "2_2") (pintype "passive"))
      (node (ref "R36") (pin "1") (pinfunction "TOP_1") (pintype "passive"))
      (node (ref "U1") (pin "11") (pinfunction "VSS_11") (pintype "power_in"))
      (node (ref "U1") (pin "26") (pinfunction "AVSS_26") (pintype "power_in"))
      (node (ref "U1") (pin "31") (pinfunction "VSS_31") (pintype "power_in"))
      (node (ref "U1") (pin "51") (pinfunction "VSS_51") (pintype "power_in"))
      (node (ref "U1") (pin "57") (pinfunction "VSSRX_57") (pintype "power_in"))
      (node (ref "U1") (pin "64") (pinfunction "VSSTX_64") (pintype "power_in"))
      (node (ref "U1") (pin "67") (pinfunction "VSSPLL_67") (pintype "power_in"))
      (node (ref "U1") (pin "70") (pinfunction "VSS_70") (pintype "power_in"))
      (node (ref "U2") (pin "1") (pinfunction "GND_1") (pintype "power_in"))
      (node (ref "U3") (pin "2") (pinfunction "GND_2") (pintype "power_in"))
    )
    (net (code "34") (name "Net-(*1-CP1)") (class "Default")
      (node (ref "*1") (pin "37") (pinfunction "CP1_37") (pintype "passive"))
      (node (ref "C15") (pin "2") (pinfunction "2_2") (pintype "passive"))
    )
    (net (code "35") (name "Net-(*1-CP2)") (class "Default")
      (node (ref "*1") (pin "38") (pinfunction "CP2_38") (pintype "passive"))
      (node (ref "C15") (pin "1") (pinfunction "1_1") (pintype "passive"))
    )
    (net (code "36") (name "Net-(*1-OUT1A)") (class "Default")
      (node (ref "*1") (pin "6") (pinfunction "OUT1A_6") (pintype "output"))
      (node (ref "J1") (pin "1") (pinfunction "1_1") (pintype "passive"))
    )
    (net (code "37") (name "Net-(*1-OUT1B)") (class "Default")
      (node (ref "*1") (pin "40") (pinfunction "OUT1B_40") (pintype "output"))
      (node (ref "J1") (pin "2") (pinfunction "2_2") (pintype "passive"))
    )
    (net (code "38") (name "Net-(*1-OUT2A)") (class "Default")
      (node (ref "*1") (pin "18") (pinfunction "OUT2A_18") (pintype "output"))
      (node (ref "J1") (pin "4") (pinfunction "4_4") (pintype "passive"))
    )
    (net (code "39") (name "Net-(*1-OUT2B)") (class "Default")
      (node (ref "*1") (pin "28") (pinfunction "OUT2B_28") (pintype "output"))
      (node (ref "J1") (pin "3") (pinfunction "3_3") (pintype "passive"))
    )
    (net (code "40") (name "Net-(*1-PFD)") (class "Default")
      (node (ref "*1") (pin "9") (pinfunction "PFD_9") (pintype "passive"))
      (node (ref "C13") (pin "2") (pinfunction "2_2") (pintype "passive"))
      (node (ref "R15") (pin "1") (pinfunction "1_1") (pintype "passive"))
      (node (ref "R22") (pin "2") (pinfunction "2_2") (pintype "passive"))
    )
    (net (code "41") (name "Net-(*1-RC1)") (class "Default")
      (node (ref "*1") (pin "10") (pinfunction "RC1_10") (pintype "passive"))
      (node (ref "C11") (pin "2") (pinfunction "2_2") (pintype "passive"))
      (node (ref "R14") (pin "2") (pinfunction "2_2") (pintype "passive"))
    )
    (net (code "42") (name "Net-(*1-RC2)") (class "Default")
      (node (ref "*1") (pin "15") (pinfunction "RC2_15") (pintype "passive"))
      (node (ref "C10") (pin "2") (pinfunction "2_2") (pintype "passive"))
      (node (ref "R13") (pin "2") (pinfunction "2_2") (pintype "passive"))
    )
    (net (code "43") (name "Net-(*1-REF)") (class "Default")
      (node (ref "*1") (pin "14") (pinfunction "REF_14") (pintype "input"))
      (node (ref "C12") (pin "1") (pinfunction "1_1") (pintype "passive"))
      (node (ref "R16") (pin "3") (pinfunction "TAP_3") (pintype "passive"))
    )
    (net (code "44") (name "Net-(*1-SENSE1)") (class "Default")
      (node (ref "*1") (pin "3") (pinfunction "SENSE1_3") (pintype "input"))
      (node (ref "C9") (pin "2") (pinfunction "2_2") (pintype "passive"))
      (node (ref "R12") (pin "2") (pinfunction "2_2") (pintype "passive"))
    )
    (net (code "45") (name "Net-(*1-SENSE2)") (class "Default")
      (node (ref "*1") (pin "21") (pinfunction "SENSE2_21") (pintype "input"))
      (node (ref "C8") (pin "2") (pinfunction "2_2") (pintype "passive"))
      (node (ref "R11") (pin "2") (pinfunction "2_2") (pintype "passive"))
    )
    (net (code "46") (name "Net-(*1-VCP)") (class "Default")
      (node (ref "*1") (pin "36") (pinfunction "VCP_36") (pintype "passive"))
      (node (ref "C7") (pin "1") (pinfunction "1_1") (pintype "passive"))
    )
    (net (code "47") (name "Net-(*1-VREG)") (class "Default")
      (node (ref "*1") (pin "32") (pinfunction "VREG_32") (pintype "passive"))
      (node (ref "C14") (pin "2") (pinfunction "2_2") (pintype "passive"))
    )
    (net (code "48") (name "Net-(*2-Pad9)") (class "Default")
      (node (ref "*2") (pin "9") (pintype "passive"))
      (node (ref "R10") (pin "2") (pinfunction "2_2") (pintype "passive"))
    )
    (net (code "49") (name "Net-(*2-Pad12)") (class "Default")
      (node (ref "*2") (pin "12") (pintype "passive"))
      (node (ref "R9") (pin "2") (pinfunction "2_2") (pintype "passive"))
    )
    (net (code "50") (name "Net-(*2-RCT)") (class "Default")
      (node (ref "*2") (pin "6") (pinfunction "RCT_6") (pintype "passive"))
      (node (ref "C17") (pin "2") (pinfunction "2_2") (pintype "passive"))
      (node (ref "R17") (pin "1") (pinfunction "1_1") (pintype "passive"))
      (node (ref "R18") (pin "1") (pinfunction "1_1") (pintype "passive"))
    )
    (net (code "51") (name "Net-(*2-Rx+)") (class "Default")
      (node (ref "*2") (pin "8") (pinfunction "Rx+_8") (pintype "passive"))
      (node (ref "R18") (pin "2") (pinfunction "2_2") (pintype "passive"))
      (node (ref "U1") (pin "59") (pinfunction "TPIN+_59") (pintype "input"))
    )
    (net (code "52") (name "Net-(*2-Rx-)") (class "Default")
      (node (ref "*2") (pin "7") (pinfunction "Rx-_7") (pintype "passive"))
      (node (ref "R17") (pin "2") (pinfunction "2_2") (pintype "passive"))
      (node (ref "U1") (pin "58") (pinfunction "TPIN-_58") (pintype "input"))
    )
    (net (code "53") (name "Net-(*2-TCT)") (class "Default")
      (node (ref "*2") (pin "3") (pinfunction "TCT_3") (pintype "passive"))
      (node (ref "C18") (pin "2") (pinfunction "2_2") (pintype "passive"))
      (node (ref "L1") (pin "2") (pinfunction "2_2") (pintype "passive"))
      (node (ref "R19") (pin "1") (pinfunction "1_1") (pintype "passive"))
      (node (ref "R20") (pin "1") (pinfunction "1_1") (pintype "passive"))
    )
    (net (code "54") (name "Net-(*2-Tx+)") (class "Default")
      (node (ref "*2") (pin "1") (pinfunction "Tx+_1") (pintype "passive"))
      (node (ref "R20") (pin "2") (pinfunction "2_2") (pintype "passive"))
      (node (ref "U1") (pin "63") (pinfunction "TPOUT+_63") (pintype "output"))
    )
    (net (code "55") (name "Net-(*2-Tx-)") (class "Default")
      (node (ref "*2") (pin "2") (pinfunction "Tx-_2") (pintype "passive"))
      (node (ref "R19") (pin "2") (pinfunction "2_2") (pintype "passive"))
      (node (ref "U1") (pin "62") (pinfunction "TPOUT-_62") (pintype "output"))
    )
    (net (code "56") (name "Net-(*3-CP1)") (class "Default")
      (node (ref "*3") (pin "37") (pinfunction "CP1_37") (pintype "passive"))
      (node (ref "C32") (pin "2") (pinfunction "2_2") (pintype "passive"))
    )
    (net (code "57") (name "Net-(*3-CP2)") (class "Default")
      (node (ref "*3") (pin "38") (pinfunction "CP2_38") (pintype "passive"))
      (node (ref "C32") (pin "1") (pinfunction "1_1") (pintype "passive"))
    )
    (net (code "58") (name "Net-(*3-OUT1A)") (class "Default")
      (node (ref "*3") (pin "6") (pinfunction "OUT1A_6") (pintype "output"))
      (node (ref "J2") (pin "1") (pinfunction "1_1") (pintype "passive"))
    )
    (net (code "59") (name "Net-(*3-OUT1B)") (class "Default")
      (node (ref "*3") (pin "40") (pinfunction "OUT1B_40") (pintype "output"))
      (node (ref "J2") (pin "2") (pinfunction "2_2") (pintype "passive"))
    )
    (net (code "60") (name "Net-(*3-OUT2A)") (class "Default")
      (node (ref "*3") (pin "18") (pinfunction "OUT2A_18") (pintype "output"))
      (node (ref "J2") (pin "4") (pinfunction "4_4") (pintype "passive"))
    )
    (net (code "61") (name "Net-(*3-OUT2B)") (class "Default")
      (node (ref "*3") (pin "28") (pinfunction "OUT2B_28") (pintype "output"))
      (node (ref "J2") (pin "3") (pinfunction "3_3") (pintype "passive"))
    )
    (net (code "62") (name "Net-(*3-PFD)") (class "Default")
      (node (ref "*3") (pin "9") (pinfunction "PFD_9") (pintype "passive"))
      (node (ref "C30") (pin "2") (pinfunction "2_2") (pintype "passive"))
      (node (ref "R28") (pin "1") (pinfunction "1_1") (pintype "passive"))
      (node (ref "R30") (pin "2") (pinfunction "2_2") (pintype "passive"))
    )
    (net (code "63") (name "Net-(*3-RC1)") (class "Default")
      (node (ref "*3") (pin "10") (pinfunction "RC1_10") (pintype "passive"))
      (node (ref "C28") (pin "2") (pinfunction "2_2") (pintype "passive"))
      (node (ref "R26") (pin "2") (pinfunction "2_2") (pintype "passive"))
    )
    (net (code "64") (name "Net-(*3-RC2)") (class "Default")
      (node (ref "*3") (pin "15") (pinfunction "RC2_15") (pintype "passive"))
      (node (ref "C27") (pin "2") (pinfunction "2_2") (pintype "passive"))
      (node (ref "R25") (pin "2") (pinfunction "2_2") (pintype "passive"))
    )
    (net (code "65") (name "Net-(*3-REF)") (class "Default")
      (node (ref "*3") (pin "14") (pinfunction "REF_14") (pintype "input"))
      (node (ref "C29") (pin "1") (pinfunction "1_1") (pintype "passive"))
      (node (ref "R27") (pin "3") (pinfunction "TAP_3") (pintype "passive"))
    )
    (net (code "66") (name "Net-(*3-SENSE1)") (class "Default")
      (node (ref "*3") (pin "3") (pinfunction "SENSE1_3") (pintype "input"))
      (node (ref "C26") (pin "2") (pinfunction "2_2") (pintype "passive"))
      (node (ref "R24") (pin "2") (pinfunction "2_2") (pintype "passive"))
    )
    (net (code "67") (name "Net-(*3-SENSE2)") (class "Default")
      (node (ref "*3") (pin "21") (pinfunction "SENSE2_21") (pintype "input"))
      (node (ref "C25") (pin "2") (pinfunction "2_2") (pintype "passive"))
      (node (ref "R23") (pin "2") (pinfunction "2_2") (pintype "passive"))
    )
    (net (code "68") (name "Net-(*3-VCP)") (class "Default")
      (node (ref "*3") (pin "36") (pinfunction "VCP_36") (pintype "passive"))
      (node (ref "C19") (pin "1") (pinfunction "1_1") (pintype "passive"))
    )
    (net (code "69") (name "Net-(*3-VREG)") (class "Default")
      (node (ref "*3") (pin "32") (pinfunction "VREG_32") (pintype "passive"))
      (node (ref "C31") (pin "2") (pinfunction "2_2") (pintype "passive"))
    )
    (net (code "70") (name "Net-(*4-CP1)") (class "Default")
      (node (ref "*4") (pin "37") (pinfunction "CP1_37") (pintype "passive"))
      (node (ref "C40") (pin "2") (pinfunction "2_2") (pintype "passive"))
    )
    (net (code "71") (name "Net-(*4-CP2)") (class "Default")
      (node (ref "*4") (pin "38") (pinfunction "CP2_38") (pintype "passive"))
      (node (ref "C40") (pin "1") (pinfunction "1_1") (pintype "passive"))
    )
    (net (code "72") (name "Net-(*4-OUT1A)") (class "Default")
      (node (ref "*4") (pin "6") (pinfunction "OUT1A_6") (pintype "output"))
      (node (ref "J4") (pin "1") (pinfunction "1_1") (pintype "passive"))
    )
    (net (code "73") (name "Net-(*4-OUT1B)") (class "Default")
      (node (ref "*4") (pin "40") (pinfunction "OUT1B_40") (pintype "output"))
      (node (ref "J4") (pin "2") (pinfunction "2_2") (pintype "passive"))
    )
    (net (code "74") (name "Net-(*4-OUT2A)") (class "Default")
      (node (ref "*4") (pin "18") (pinfunction "OUT2A_18") (pintype "output"))
      (node (ref "J4") (pin "4") (pinfunction "4_4") (pintype "passive"))
    )
    (net (code "75") (name "Net-(*4-OUT2B)") (class "Default")
      (node (ref "*4") (pin "28") (pinfunction "OUT2B_28") (pintype "output"))
      (node (ref "J4") (pin "3") (pinfunction "3_3") (pintype "passive"))
    )
    (net (code "76") (name "Net-(*4-PFD)") (class "Default")
      (node (ref "*4") (pin "9") (pinfunction "PFD_9") (pintype "passive"))
      (node (ref "C38") (pin "2") (pinfunction "2_2") (pintype "passive"))
      (node (ref "R35") (pin "1") (pinfunction "1_1") (pintype "passive"))
      (node (ref "R37") (pin "2") (pinfunction "2_2") (pintype "passive"))
    )
    (net (code "77") (name "Net-(*4-RC1)") (class "Default")
      (node (ref "*4") (pin "10") (pinfunction "RC1_10") (pintype "passive"))
      (node (ref "C37") (pin "2") (pinfunction "2_2") (pintype "passive"))
      (node (ref "R34") (pin "2") (pinfunction "2_2") (pintype "passive"))
    )
    (net (code "78") (name "Net-(*4-RC2)") (class "Default")
      (node (ref "*4") (pin "15") (pinfunction "RC2_15") (pintype "passive"))
      (node (ref "C36") (pin "2") (pinfunction "2_2") (pintype "passive"))
      (node (ref "R33") (pin "2") (pinfunction "2_2") (pintype "passive"))
    )
    (net (code "79") (name "Net-(*4-REF)") (class "Default")
      (node (ref "*4") (pin "14") (pinfunction "REF_14") (pintype "input"))
      (node (ref "C41") (pin "1") (pinfunction "1_1") (pintype "passive"))
      (node (ref "R36") (pin "3") (pinfunction "TAP_3") (pintype "passive"))
    )
    (net (code "80") (name "Net-(*4-SENSE1)") (class "Default")
      (node (ref "*4") (pin "3") (pinfunction "SENSE1_3") (pintype "input"))
      (node (ref "C35") (pin "2") (pinfunction "2_2") (pintype "passive"))
      (node (ref "R32") (pin "2") (pinfunction "2_2") (pintype "passive"))
    )
    (net (code "81") (name "Net-(*4-SENSE2)") (class "Default")
      (node (ref "*4") (pin "21") (pinfunction "SENSE2_21") (pintype "input"))
      (node (ref "C34") (pin "2") (pinfunction "2_2") (pintype "passive"))
      (node (ref "R31") (pin "2") (pinfunction "2_2") (pintype "passive"))
    )
    (net (code "82") (name "Net-(*4-VCP)") (class "Default")
      (node (ref "*4") (pin "36") (pinfunction "VCP_36") (pintype "passive"))
      (node (ref "C33") (pin "1") (pinfunction "1_1") (pintype "passive"))
    )
    (net (code "83") (name "Net-(*4-VREG)") (class "Default")
      (node (ref "*4") (pin "32") (pinfunction "VREG_32") (pintype "passive"))
      (node (ref "C39") (pin "2") (pinfunction "2_2") (pintype "passive"))
    )
    (net (code "84") (name "Net-(D1-A)") (class "Default")
      (node (ref "C2") (pin "2") (pinfunction "2_2") (pintype "passive"))
      (node (ref "D1") (pin "1") (pinfunction "A_1") (pintype "passive"))
      (node (ref "R7") (pin "1") (pinfunction "1_1") (pintype "passive"))
      (node (ref "R8") (pin "2") (pinfunction "2_2") (pintype "passive"))
    )
    (net (code "85") (name "Net-(D2-A)") (class "Default")
      (node (ref "D2") (pin "1") (pinfunction "A_1") (pintype "passive"))
      (node (ref "R38") (pin "2") (pinfunction "2_2") (pintype "passive"))
    )
    (net (code "86") (name "Net-(D3-A)") (class "Default")
      (node (ref "D3") (pin "1") (pinfunction "A_1") (pintype "passive"))
      (node (ref "R39") (pin "2") (pinfunction "2_2") (pintype "passive"))
    )
    (net (code "87") (name "Net-(D4-A)") (class "Default")
      (node (ref "D4") (pin "1") (pinfunction "A_1") (pintype "passive"))
      (node (ref "R40") (pin "2") (pinfunction "2_2") (pintype "passive"))
    )
    (net (code "88") (name "Net-(D5-A)") (class "Default")
      (node (ref "D5") (pin "1") (pinfunction "A_1") (pintype "passive"))
      (node (ref "R41") (pin "2") (pinfunction "2_2") (pintype "passive"))
    )
    (net (code "89") (name "Net-(D6-A)") (class "Default")
      (node (ref "D6") (pin "1") (pinfunction "A_1") (pintype "passive"))
      (node (ref "R42") (pin "2") (pinfunction "2_2") (pintype "passive"))
    )
    (net (code "90") (name "Net-(J1-Pad6)") (class "Default")
      (node (ref "J1") (pin "6") (pinfunction "6_6") (pintype "passive"))
      (node (ref "R5") (pin "1") (pinfunction "1_1") (pintype "passive"))
    )
    (net (code "91") (name "Net-(J1-Pad8)") (class "Default")
      (node (ref "J1") (pin "8") (pinfunction "8_8") (pintype "passive"))
      (node (ref "R6") (pin "1") (pinfunction "1_1") (pintype "passive"))
    )
    (net (code "92") (name "Net-(J2-Pad6)") (class "Default")
      (node (ref "J2") (pin "6") (pinfunction "6_6") (pintype "passive"))
      (node (ref "R4") (pin "1") (pinfunction "1_1") (pintype "passive"))
    )
    (net (code "93") (name "Net-(J2-Pad8)") (class "Default")
      (node (ref "J2") (pin "8") (pinfunction "8_8") (pintype "passive"))
      (node (ref "R3") (pin "1") (pinfunction "1_1") (pintype "passive"))
    )
    (net (code "94") (name "Net-(J4-Pad6)") (class "Default")
      (node (ref "J4") (pin "6") (pinfunction "6_6") (pintype "passive"))
      (node (ref "R2") (pin "1") (pinfunction "1_1") (pintype "passive"))
    )
    (net (code "95") (name "Net-(J4-Pad8)") (class "Default")
      (node (ref "J4") (pin "8") (pinfunction "8_8") (pintype "passive"))
      (node (ref "R1") (pin "1") (pinfunction "1_1") (pintype "passive"))
    )
    (net (code "96") (name "Net-(U1-OSC1{slash}CLKI)") (class "Default")
      (node (ref "C6") (pin "2") (pinfunction "2_2") (pintype "passive"))
      (node (ref "U1") (pin "49") (pinfunction "OSC1/CLKI_49") (pintype "input"))
      (node (ref "Y2") (pin "2") (pinfunction "OSC2_2") (pintype "passive"))
    )
    (net (code "97") (name "Net-(U1-OSC2{slash}CLKO)") (class "Default")
      (node (ref "C5") (pin "1") (pinfunction "1_1") (pintype "passive"))
      (node (ref "U1") (pin "50") (pinfunction "OSC2/CLKO_50") (pintype "output"))
      (node (ref "Y2") (pin "1") (pinfunction "OSC1_1") (pintype "passive"))
    )
    (net (code "98") (name "Net-(U1-RA0{slash}LEDA{slash}AN0)") (class "Default")
      (node (ref "R9") (pin "1") (pinfunction "1_1") (pintype "passive"))
      (node (ref "U1") (pin "30") (pinfunction "RA0/LEDA/AN0_30") (pintype "bidirectional"))
    )
    (net (code "99") (name "Net-(U1-RA1{slash}LEDB{slash}AN1)") (class "Default")
      (node (ref "R10") (pin "1") (pinfunction "1_1") (pintype "passive"))
      (node (ref "U1") (pin "29") (pinfunction "RA1/LEDB/AN1_29") (pintype "bidirectional"))
    )
    (net (code "100") (name "Net-(U1-RBIAS)") (class "Default")
      (node (ref "R21") (pin "2") (pinfunction "2_2") (pintype "passive"))
      (node (ref "U1") (pin "65") (pinfunction "RBIAS_65") (pintype "input"))
    )
    (net (code "101") (name "Net-(U1-RC0{slash}T1OSO{slash}T13CKI)") (class "Default")
      (node (ref "C3") (pin "1") (pinfunction "1_1") (pintype "passive"))
      (node (ref "U1") (pin "36") (pinfunction "RC0/T1OSO/T13CKI_36") (pintype "bidirectional"))
      (node (ref "Y1") (pin "1") (pinfunction "OSC1_1") (pintype "passive"))
    )
    (net (code "102") (name "Net-(U1-RC1{slash}T1OSI{slash}ECCP2{slash}P2A)") (class "Default")
      (node (ref "C4") (pin "2") (pinfunction "2_2") (pintype "passive"))
      (node (ref "U1") (pin "35") (pinfunction "RC1/T1OSI/ECCP2/P2A_35") (pintype "bidirectional"))
      (node (ref "Y1") (pin "2") (pinfunction "OSC2_2") (pintype "passive"))
    )
    (net (code "103") (name "Net-(U1-RC6{slash}TX1{slash}CK1)") (class "Default")
      (node (ref "R42") (pin "1") (pinfunction "1_1") (pintype "passive"))
      (node (ref "U1") (pin "37") (pinfunction "RC6/TX1/CK1_37") (pintype "bidirectional"))
    )
    (net (code "104") (name "Net-(U1-RC7{slash}RX1{slash}DT1)") (class "Default")
      (node (ref "R41") (pin "1") (pinfunction "1_1") (pintype "passive"))
      (node (ref "U1") (pin "38") (pinfunction "RC7/RX1/DT1_38") (pintype "bidirectional"))
    )
    (net (code "105") (name "Net-(U1-RD0)") (class "Default")
      (node (ref "R40") (pin "1") (pinfunction "1_1") (pintype "passive"))
      (node (ref "U1") (pin "72") (pinfunction "RD0_72") (pintype "bidirectional"))
    )
    (net (code "106") (name "Net-(U1-RD1)") (class "Default")
      (node (ref "R39") (pin "1") (pinfunction "1_1") (pintype "passive"))
      (node (ref "U1") (pin "69") (pinfunction "RD1_69") (pintype "bidirectional"))
    )
    (net (code "107") (name "Net-(U1-RD2)") (class "Default")
      (node (ref "R38") (pin "1") (pinfunction "1_1") (pintype "passive"))
      (node (ref "U1") (pin "68") (pinfunction "RD2_68") (pintype "bidirectional"))
    )
    (net (code "108") (name "Net-(U1-VDDCORE{slash}VCAP)") (class "Default")
      (node (ref "C16") (pin "1") (pinfunction "1_1") (pintype "passive"))
      (node (ref "U1") (pin "12") (pinfunction "VDDCORE/VCAP_12") (pintype "power_in"))
    )
    (net (code "109") (name "VCC") (class "Default")
      (node (ref "*1") (pin "16") (pinfunction "VDD_16") (pintype "power_in"))
      (node (ref "*3") (pin "16") (pinfunction "VDD_16") (pintype "power_in"))
      (node (ref "*4") (pin "16") (pinfunction "VDD_16") (pintype "power_in"))
      (node (ref "C20") (pin "1") (pinfunction "1_1") (pintype "passive"))
      (node (ref "C21") (pin "1") (pinfunction "1_1") (pintype "passive"))
      (node (ref "C22") (pin "1") (pinfunction "1_1") (pintype "passive"))
      (node (ref "C23") (pin "1") (pinfunction "1_1") (pintype "passive"))
      (node (ref "C24") (pin "1") (pinfunction "1_1") (pintype "passive"))
      (node (ref "D1") (pin "2") (pinfunction "K_2") (pintype "passive"))
      (node (ref "J1") (pin "7") (pinfunction "7_7") (pintype "passive"))
      (node (ref "J2") (pin "7") (pinfunction "7_7") (pintype "passive"))
      (node (ref "J4") (pin "7") (pinfunction "7_7") (pintype "passive"))
      (node (ref "L1") (pin "1") (pinfunction "1_1") (pintype "passive"))
      (node (ref "P1") (pin "2") (pinfunction "2_2") (pintype "passive"))
      (node (ref "P2") (pin "1") (pinfunction "1_1") (pintype "passive"))
      (node (ref "R16") (pin "2") (pinfunction "BOT_2") (pintype "passive"))
      (node (ref "R22") (pin "1") (pinfunction "1_1") (pintype "passive"))
      (node (ref "R27") (pin "2") (pinfunction "BOT_2") (pintype "passive"))
      (node (ref "R30") (pin "1") (pinfunction "1_1") (pintype "passive"))
      (node (ref "R36") (pin "2") (pinfunction "BOT_2") (pintype "passive"))
      (node (ref "R37") (pin "1") (pinfunction "1_1") (pintype "passive"))
      (node (ref "R7") (pin "2") (pinfunction "2_2") (pintype "passive"))
      (node (ref "U1") (pin "24") (pinfunction "ENVREG_24") (pintype "input"))
      (node (ref "U1") (pin "25") (pinfunction "AVDD_25") (pintype "power_in"))
      (node (ref "U1") (pin "32") (pinfunction "VDD_32") (pintype "power_in"))
      (node (ref "U1") (pin "48") (pinfunction "VDD_48") (pintype "power_in"))
      (node (ref "U1") (pin "60") (pinfunction "VDDRX_60") (pintype "power_in"))
      (node (ref "U1") (pin "61") (pinfunction "VDDTX_61") (pintype "power_in"))
      (node (ref "U1") (pin "66") (pinfunction "VDDPLL_66") (pintype "power_in"))
      (node (ref "U1") (pin "71") (pinfunction "VDD_71") (pintype "power_in"))
      (node (ref "U2") (pin "4") (pinfunction "OUT_4") (pintype "power_in"))
    )
    (net (code "110") (name "unconnected-(J1-Pad9)") (class "Default")
      (node (ref "J1") (pin "9") (pinfunction "9_9") (pintype "passive"))
    )
    (net (code "111") (name "unconnected-(J2-Pad9)") (class "Default")
      (node (ref "J2") (pin "9") (pinfunction "9_9") (pintype "passive"))
    )
    (net (code "112") (name "unconnected-(J4-Pad9)") (class "Default")
      (node (ref "J4") (pin "9") (pinfunction "9_9") (pintype "passive"))
    )
    (net (code "113") (name "unconnected-(P1-Pad6)") (class "Default")
      (node (ref "P1") (pin "6") (pinfunction "6_6") (pintype "passive"))
    )
    (net (code "114") (name "unconnected-(U1-RA5{slash}AN4-Pad33)") (class "Default")
      (node (ref "U1") (pin "33") (pinfunction "RA5/AN4_33") (pintype "bidirectional"))
    )
    (net (code "115") (name "unconnected-(U1-RE6{slash}P1B-Pad74)") (class "Default")
      (node (ref "U1") (pin "74") (pinfunction "RE6/P1B_74") (pintype "bidirectional"))
    )
    (net (code "116") (name "unconnected-(U1-RF6{slash}AN11-Pad14)") (class "Default")
      (node (ref "U1") (pin "14") (pinfunction "RF6/AN11_14") (pintype "bidirectional"))
    )
    (net (code "117") (name "unconnected-(U1-RG1{slash}TX2{slash}CK2-Pad55)") (class "Default")
      (node (ref "U1") (pin "55") (pinfunction "RG1/TX2/CK2_55") (pintype "bidirectional"))
    )
    (net (code "118") (name "unconnected-(U1-RG2{slash}RX2{slash}DT2-Pad42)") (class "Default")
      (node (ref "U1") (pin "42") (pinfunction "RG2/RX2/DT2_42") (pintype "bidirectional"))
    )
    (net (code "119") (name "unconnected-(U1-RG4{slash}CCP5{slash}P1D-Pad10)") (class "Default")
      (node (ref "U1") (pin "10") (pinfunction "RG4/CCP5/P1D_10") (pintype "bidirectional"))
    )
    (net (code "120") (name "unconnected-(U1-RH0-Pad79)") (class "Default")
      (node (ref "U1") (pin "79") (pinfunction "RH0_79") (pintype "bidirectional"))
    )
    (net (code "121") (name "unconnected-(U1-RH1-Pad80)") (class "Default")
      (node (ref "U1") (pin "80") (pinfunction "RH1_80") (pintype "bidirectional"))
    )
    (net (code "122") (name "unconnected-(U1-RH2-Pad1)") (class "Default")
      (node (ref "U1") (pin "1") (pinfunction "RH2_1") (pintype "bidirectional"))
    )
    (net (code "123") (name "unconnected-(U1-RH3-Pad2)") (class "Default")
      (node (ref "U1") (pin "2") (pinfunction "RH3_2") (pintype "bidirectional"))
    )
    (net (code "124") (name "unconnected-(U1-RH4{slash}AN12{slash}P3C-Pad22)") (class "Default")
      (node (ref "U1") (pin "22") (pinfunction "RH4/AN12/P3C_22") (pintype "bidirectional"))
    )
    (net (code "125") (name "unconnected-(U1-RH5{slash}AN13{slash}P3B-Pad21)") (class "Default")
      (node (ref "U1") (pin "21") (pinfunction "RH5/AN13/P3B_21") (pintype "bidirectional"))
    )
    (net (code "126") (name "unconnected-(U1-RH6{slash}AN14{slash}P1C-Pad20)") (class "Default")
      (node (ref "U1") (pin "20") (pinfunction "RH6/AN14/P1C_20") (pintype "bidirectional"))
    )
    (net (code "127") (name "unconnected-(U1-RH7{slash}AN15{slash}P1B-Pad19)") (class "Default")
      (node (ref "U1") (pin "19") (pinfunction "RH7/AN15/P1B_19") (pintype "bidirectional"))
    )
    (net (code "128") (name "unconnected-(U1-RJ4-Pad39)") (class "Default")
      (node (ref "U1") (pin "39") (pinfunction "RJ4_39") (pintype "bidirectional"))
    )
    (net (code "129") (name "unconnected-(U1-RJ5-Pad40)") (class "Default")
      (node (ref "U1") (pin "40") (pinfunction "RJ5_40") (pintype "bidirectional"))
    )
  )
)
